# USB.net
KiCad netlist of a schematic drawn in Altium Designer
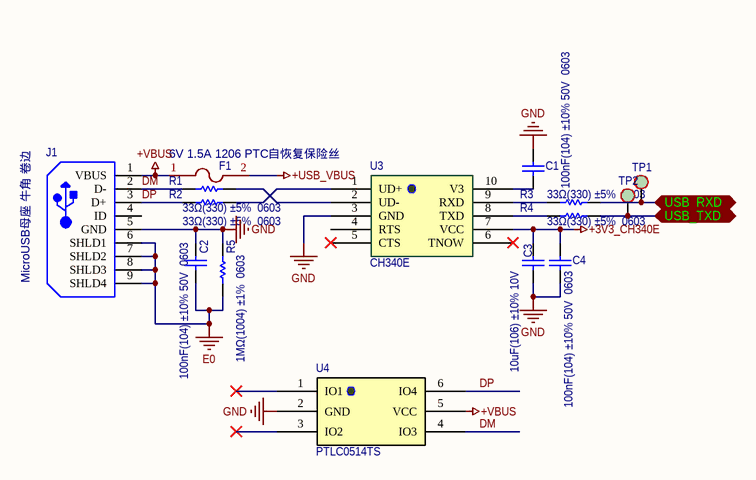
[diagram p0: USB.SchDoc]

(export (version "E")
  (design (tool "Eeschema 10.0.6"))
  (components
    (comp (ref "C1")
      (value "100nF(104) ±10% 50V  0603")
      (footprint "C0603")
      (description "0603贴片电容")
      (fields (field (name "PUBLISHER") "Altium Limited"))
      (libsource (lib "Miscellaneous Devices") (part "Cap"))
    )
    (comp (ref "C2")
      (value "100nF(104) ±10% 50V  0603")
      (footprint "C0603")
      (description "0603贴片电容")
      (fields (field (name "PUBLISHER") "Altium Limited"))
      (libsource (lib "Miscellaneous Devices") (part "Cap"))
    )
    (comp (ref "C3")
      (value "10uF(106) ±10% 10V")
      (footprint "C0603")
      (description "0603贴片电容")
      (fields (field (name "PUBLISHER") "Altium Limited"))
      (libsource (lib "Miscellaneous Devices") (part "Cap"))
    )
    (comp (ref "C4")
      (value "100nF(104) ±10% 50V  0603")
      (footprint "C0603")
      (description "0603贴片电容")
      (fields (field (name "PUBLISHER") "Altium Limited"))
      (libsource (lib "Miscellaneous Devices") (part "Cap"))
    )
    (comp (ref "F1")
      (value "6V 1.5A 1206 PTC自恢复保险丝")
      (footprint "F1206")
      (description "1206 PTC自恢复保险丝")
      (fields
        (field (name "BOM_MANUFACTURER PART") "ASMD1206-150")
        (field (name "BOM_SUPPLIER PART") "C135341")
        (field (name "CONTRIBUTOR") "LCSC")
      )
      (libsource (lib "altium-import") (part "root_0_ASMD1206-150_"))
    )
    (comp (ref "J1")
      (value "MicroUSB母座 牛角 卷边")
      (footprint "MICRO USB 母座 小牛角有柱 卷边")
      (description "MicroUSB母座")
      (fields (field (name "TOLERANCE") "10%"))
      (libsource (lib "altium-import") (part "root_0_mirrored_CMP-0029-00002-1_"))
    )
    (comp (ref "R1")
      (value "33Ω(330) ±5%  0603")
      (footprint "R0603")
      (description "0603贴片电阻")
      (fields (field (name "PUBLISHER") "Altium Limited"))
      (libsource (lib "Miscellaneous Devices") (part "Res1"))
    )
    (comp (ref "R2")
      (value "33Ω(330) ±5%  0603")
      (footprint "R0603")
      (description "0603贴片电阻")
      (fields (field (name "PUBLISHER") "Altium Limited"))
      (libsource (lib "Miscellaneous Devices") (part "Res1"))
    )
    (comp (ref "R3")
      (value "33Ω(330) ±5%  0603")
      (footprint "R0603")
      (description "0603贴片电阻")
      (fields (field (name "PUBLISHER") "Altium Limited"))
      (libsource (lib "Miscellaneous Devices") (part "Res1"))
    )
    (comp (ref "R4")
      (value "33Ω(330) ±5%  0603")
      (footprint "R0603")
      (description "0603贴片电阻")
      (fields (field (name "PUBLISHER") "Altium Limited"))
      (libsource (lib "Miscellaneous Devices") (part "Res1"))
    )
    (comp (ref "R5")
      (value "1MΩ(1004) ±1%  0603")
      (footprint "R0603")
      (description "0603贴片电阻")
      (fields (field (name "PUBLISHER") "Altium Limited"))
      (libsource (lib "Miscellaneous Devices") (part "Res1"))
    )
    (comp (ref "TP1") (value "NC") (footprint "TP") (description "测试点") (libsource (lib "Tek") (part "TP")))
    (comp (ref "TP2") (value "NC") (footprint "TP") (description "测试点") (libsource (lib "Tek") (part "TP")))
    (comp (ref "U3")
      (value "CH340E")
      (footprint "MSOP-10")
      (description "USB转串口IC")
      (libsource (lib "Tek") (part "CH340E"))
    )
    (comp (ref "U4") (value "PTLC0514TS") (footprint "SOT-236") (libsource (lib "Tek") (part "PTLC0514TS")))
  )
  (nets
    (net (code "1") (name "+3V3_CH340E") (class "Default")
      (node (ref "C3") (pin "2") (pinfunction "2_2") (pintype "passive"))
      (node (ref "C4") (pin "1") (pinfunction "1_1") (pintype "passive"))
      (node (ref "U3") (pin "7") (pinfunction "VCC_7") (pintype "passive"))
    )
    (net (code "2") (name "+USB_VBUS") (class "Default")
      (node (ref "F1") (pin "2") (pinfunction "2_2") (pintype "passive"))
    )
    (net (code "3") (name "+VBUS") (class "Default")
      (node (ref "F1") (pin "1") (pinfunction "1_1") (pintype "passive"))
      (node (ref "J1") (pin "1") (pinfunction "VBUS_1") (pintype "passive"))
      (node (ref "U4") (pin "5") (pinfunction "VCC_5") (pintype "passive"))
    )
    (net (code "4") (name "/DM") (class "Default")
      (node (ref "J1") (pin "2") (pinfunction "D-_2") (pintype "passive"))
      (node (ref "R1") (pin "2") (pinfunction "2_2") (pintype "passive"))
      (node (ref "U4") (pin "4") (pinfunction "IO3_4") (pintype "passive"))
    )
    (net (code "5") (name "/DP") (class "Default")
      (node (ref "J1") (pin "3") (pinfunction "D+_3") (pintype "passive"))
      (node (ref "R2") (pin "2") (pinfunction "2_2") (pintype "passive"))
      (node (ref "U4") (pin "6") (pinfunction "IO4_6") (pintype "passive"))
    )
    (net (code "6") (name "/USB_RXD") (class "Default")
      (node (ref "R3") (pin "1") (pinfunction "1_1") (pintype "passive"))
      (node (ref "TP1") (pin "1") (pinfunction "0_1") (pintype "passive"))
    )
    (net (code "7") (name "/USB_TXD") (class "Default")
      (node (ref "R4") (pin "1") (pinfunction "1_1") (pintype "passive"))
      (node (ref "TP2") (pin "1") (pinfunction "0_1") (pintype "passive"))
    )
    (net (code "8") (name "E0") (class "Default")
      (node (ref "C2") (pin "1") (pinfunction "1_1") (pintype "passive"))
      (node (ref "J1") (pin "6") (pinfunction "SHLD1_6") (pintype "passive"))
      (node (ref "J1") (pin "7") (pinfunction "SHLD2_7") (pintype "passive"))
      (node (ref "J1") (pin "8") (pinfunction "SHLD3_8") (pintype "passive"))
      (node (ref "J1") (pin "9") (pinfunction "SHLD4_9") (pintype "passive"))
      (node (ref "R5") (pin "1") (pinfunction "1_1") (pintype "passive"))
    )
    (net (code "9") (name "GND") (class "Default")
      (node (ref "C1") (pin "1") (pinfunction "1_1") (pintype "passive"))
      (node (ref "C2") (pin "2") (pinfunction "2_2") (pintype "passive"))
      (node (ref "C3") (pin "1") (pinfunction "1_1") (pintype "passive"))
      (node (ref "C4") (pin "2") (pinfunction "2_2") (pintype "passive"))
      (node (ref "J1") (pin "5") (pinfunction "GND_5") (pintype "passive"))
      (node (ref "R5") (pin "2") (pinfunction "2_2") (pintype "passive"))
      (node (ref "U3") (pin "3") (pinfunction "GND_3") (pintype "passive"))
      (node (ref "U4") (pin "2") (pinfunction "GND_2") (pintype "passive"))
    )
    (net (code "10") (name "Net-(U3-RXD)") (class "Default")
      (node (ref "R3") (pin "2") (pinfunction "2_2") (pintype "passive"))
      (node (ref "U3") (pin "9") (pinfunction "RXD_9") (pintype "passive"))
    )
    (net (code "11") (name "Net-(U3-TXD)") (class "Default")
      (node (ref "R4") (pin "2") (pinfunction "2_2") (pintype "passive"))
      (node (ref "U3") (pin "8") (pinfunction "TXD_8") (pintype "passive"))
    )
    (net (code "12") (name "Net-(U3-UD+)") (class "Default")
      (node (ref "R2") (pin "1") (pinfunction "1_1") (pintype "passive"))
      (node (ref "U3") (pin "1") (pinfunction "UD+_1") (pintype "passive"))
    )
    (net (code "13") (name "Net-(U3-UD-)") (class "Default")
      (node (ref "R1") (pin "1") (pinfunction "1_1") (pintype "passive"))
      (node (ref "U3") (pin "2") (pinfunction "UD-_2") (pintype "passive"))
    )
    (net (code "14") (name "Net-(U3-V3)") (class "Default")
      (node (ref "C1") (pin "2") (pinfunction "2_2") (pintype "passive"))
      (node (ref "U3") (pin "10") (pinfunction "V3_10") (pintype "passive"))
    )
    (net (code "15") (name "unconnected-(J1-ID-Pad4)") (class "Default")
      (node (ref "J1") (pin "4") (pinfunction "ID_4") (pintype "passive"))
    )
    (net (code "16") (name "unconnected-(U3-CTS-Pad5)") (class "Default")
      (node (ref "U3") (pin "5") (pinfunction "CTS_5") (pintype "passive+no_connect"))
    )
    (net (code "17") (name "unconnected-(U3-RTS-Pad4)") (class "Default")
      (node (ref "U3") (pin "4") (pinfunction "RTS_4") (pintype "passive"))
    )
    (net (code "18") (name "unconnected-(U3-TNOW-Pad6)") (class "Default")
      (node (ref "U3") (pin "6") (pinfunction "TNOW_6") (pintype "passive+no_connect"))
    )
    (net (code "19") (name "unconnected-(U4-IO1-Pad1)") (class "Default")
      (node (ref "U4") (pin "1") (pinfunction "IO1_1") (pintype "passive+no_connect"))
    )
    (net (code "20") (name "unconnected-(U4-IO2-Pad3)") (class "Default")
      (node (ref "U4") (pin "3") (pinfunction "IO2_3") (pintype "passive+no_connect"))
    )
  )
)
